# Bandpass.net
KiCad netlist of a schematic drawn in Altium Designer
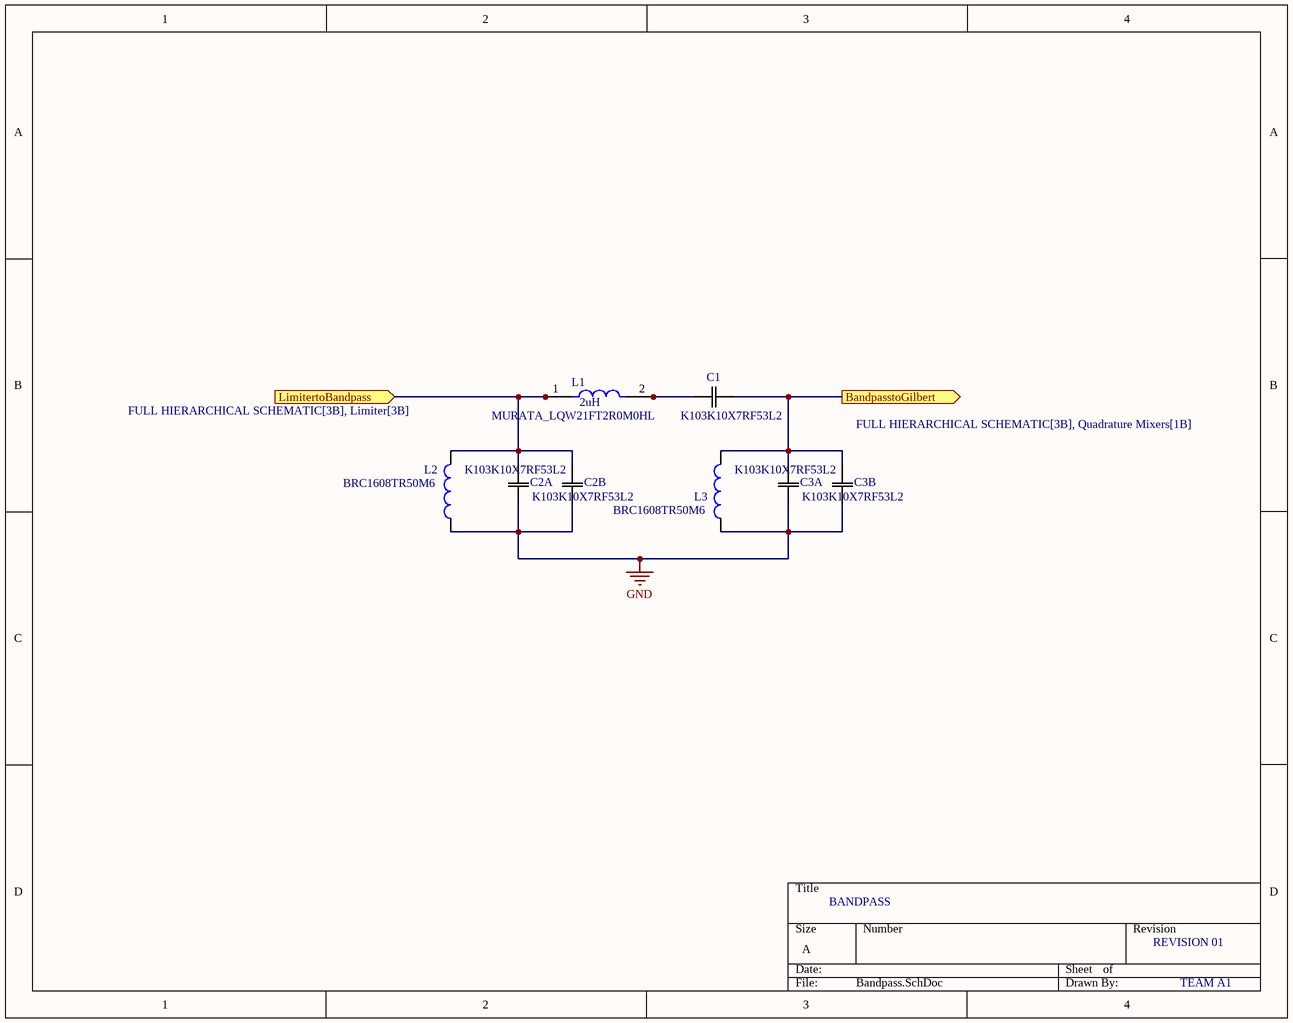
[diagram p0: Bandpass.SchDoc]

(export (version "E")
  (design (tool "Eeschema 10.0.6"))
  (components
    (comp (ref "C1")
      (value "K103K10X7RF53L2")
      (footprint "K103K10X7RF53L2_VIS")
      (description "No Description Available")
      (libsource (lib "K103K10X7RF53L2") (part "K103K10X7RF53L2"))
    )
    (comp (ref "C2A")
      (value "K103K10X7RF53L2")
      (footprint "K103K10X7RF53L2_VIS")
      (description "No Description Available")
      (libsource (lib "K103K10X7RF53L2") (part "K103K10X7RF53L2"))
    )
    (comp (ref "C2B")
      (value "K103K10X7RF53L2")
      (footprint "K103K10X7RF53L2_VIS")
      (description "No Description Available")
      (libsource (lib "K103K10X7RF53L2") (part "K103K10X7RF53L2"))
    )
    (comp (ref "C3A")
      (value "K103K10X7RF53L2")
      (footprint "K103K10X7RF53L2_VIS")
      (description "No Description Available")
      (libsource (lib "K103K10X7RF53L2") (part "K103K10X7RF53L2"))
    )
    (comp (ref "C3B")
      (value "K103K10X7RF53L2")
      (footprint "K103K10X7RF53L2_VIS")
      (description "No Description Available")
      (libsource (lib "K103K10X7RF53L2") (part "K103K10X7RF53L2"))
    )
    (comp (ref "L1")
      (value "MURATA_LQW21FT2R0M0HL")
      (footprint "MURATA_LQW21FT2R0M0HL_0")
      (description "FIXED IND 2UH 450MA POWRTRN")
      (fields (field (name "MP") "LQW21FT2R0M0HL") (field (name "MF") "Murata Electronics"))
      (libsource (lib "MURATA_LQW21FT2R0M0HL") (part "MURATA_LQW21FT2R0M0HL"))
    )
    (comp (ref "L2")
      (value "BRC1608TR50M6")
      (footprint "INDC1608X100N")
      (description "Inductor Power Chip Wirewound 500nH 20% 6MHz Ferrite 1.05A 117mOhm DCR 0603 T/R")
      (libsource (lib "BRC1608TR50M6") (part "BRC1608TR50M6"))
    )
    (comp (ref "L3")
      (value "BRC1608TR50M6")
      (footprint "INDC1608X100N")
      (description "Inductor Power Chip Wirewound 500nH 20% 6MHz Ferrite 1.05A 117mOhm DCR 0603 T/R")
      (libsource (lib "BRC1608TR50M6") (part "BRC1608TR50M6"))
    )
  )
  (nets
    (net (code "1") (name "/BandpasstoGilbert") (class "Default")
      (node (ref "C1") (pin "2") (pinfunction "2_2") (pintype "passive"))
      (node (ref "C3A") (pin "2") (pinfunction "2_2") (pintype "passive"))
      (node (ref "C3B") (pin "2") (pinfunction "2_2") (pintype "passive"))
      (node (ref "L3") (pin "2") (pinfunction "2_2") (pintype "passive"))
    )
    (net (code "2") (name "/LimitertoBandpass") (class "Default")
      (node (ref "C2A") (pin "2") (pinfunction "2_2") (pintype "passive"))
      (node (ref "C2B") (pin "2") (pinfunction "2_2") (pintype "passive"))
      (node (ref "L1") (pin "1") (pinfunction "1_1") (pintype "passive"))
      (node (ref "L2") (pin "2") (pinfunction "2_2") (pintype "passive"))
    )
    (net (code "3") (name "GND") (class "Default")
      (node (ref "C2A") (pin "1") (pinfunction "1_1") (pintype "passive"))
      (node (ref "C2B") (pin "1") (pinfunction "1_1") (pintype "passive"))
      (node (ref "C3A") (pin "1") (pinfunction "1_1") (pintype "passive"))
      (node (ref "C3B") (pin "1") (pinfunction "1_1") (pintype "passive"))
      (node (ref "L2") (pin "1") (pinfunction "1_1") (pintype "passive"))
      (node (ref "L3") (pin "1") (pinfunction "1_1") (pintype "passive"))
    )
    (net (code "4") (name "Net-(C1-Pad1)") (class "Default")
      (node (ref "C1") (pin "1") (pinfunction "1_1") (pintype "passive"))
      (node (ref "L1") (pin "2") (pinfunction "2_2") (pintype "passive"))
    )
  )
)
